# 13_eMMC_Flash.net
KiCad netlist of a schematic drawn in Altium Designer
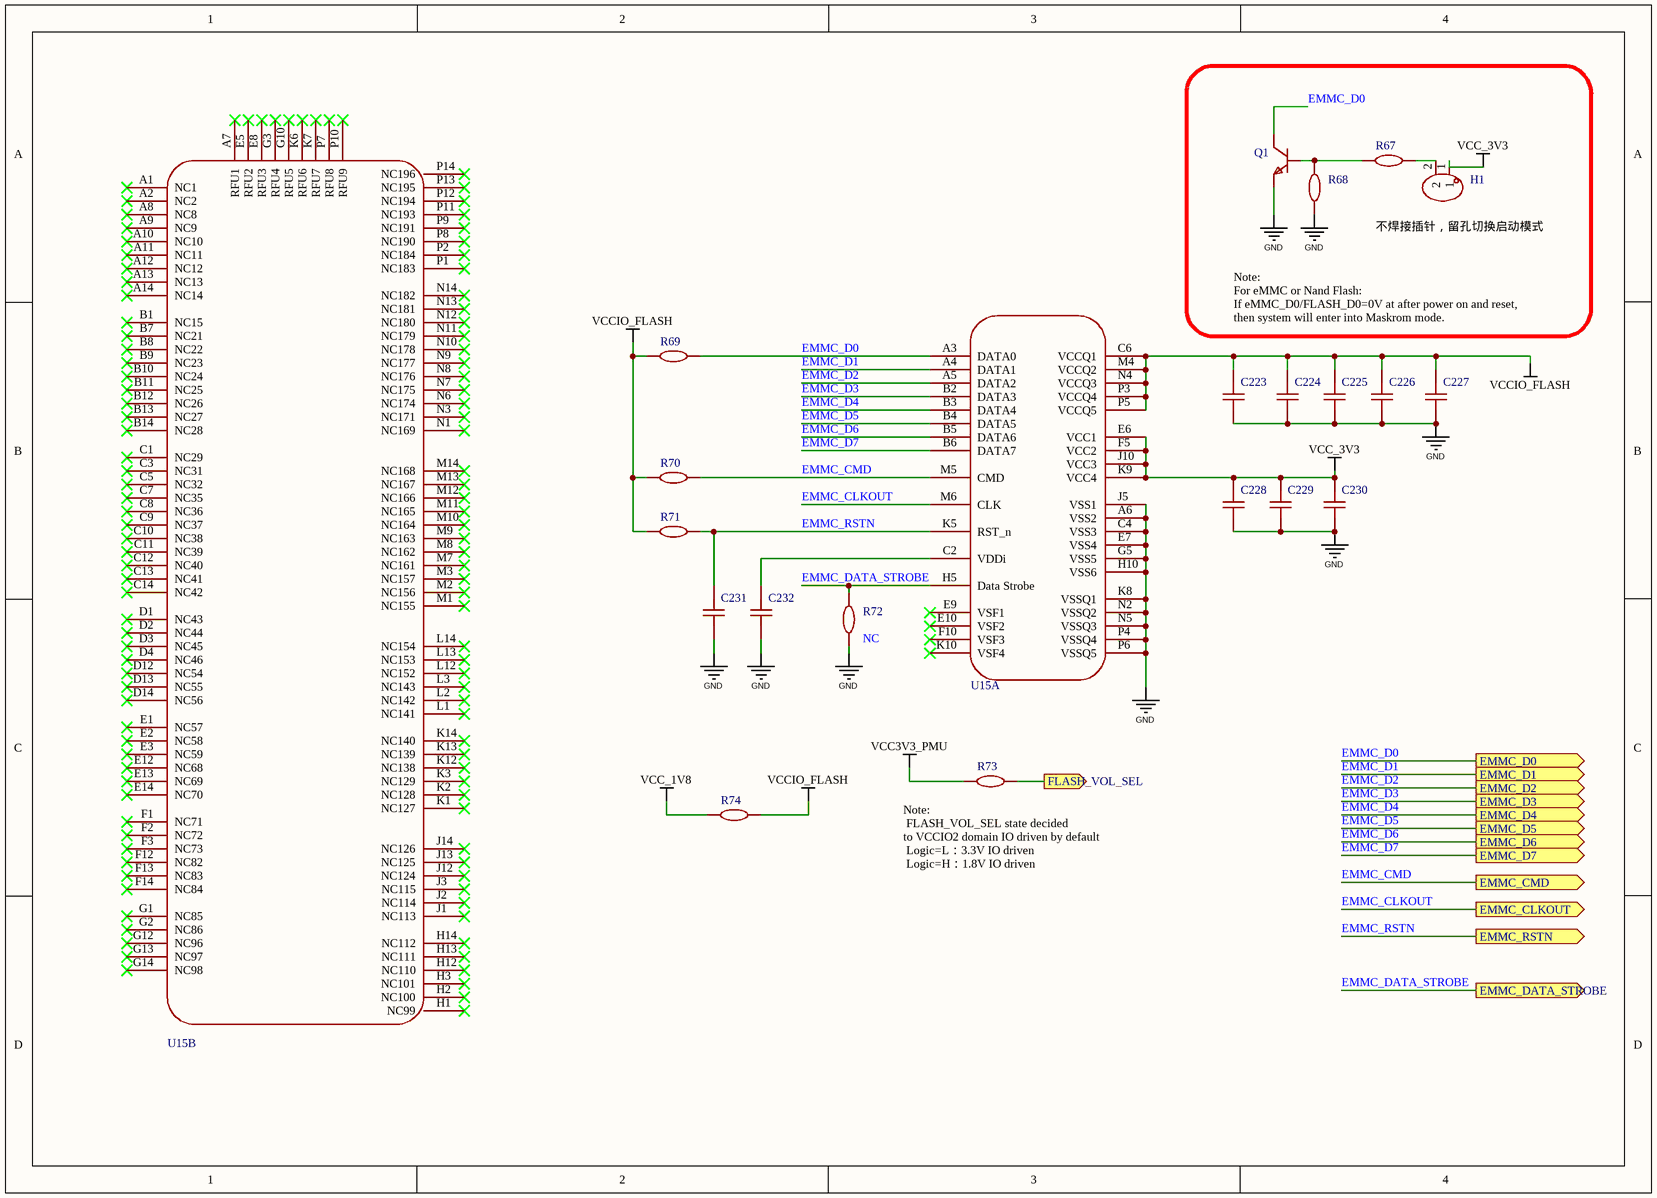
[diagram p0: 13_eMMC Flash.schdoc]

(export (version "E")
  (design (tool "Eeschema 10.0.6"))
  (components
    (comp (ref "C223")
      (value "100nF")
      (footprint "C0402")
      (description "容值:100nF;精度:±10%;额定电压:50V;材质(温度系数):X7R;")
      (fields
        (field (name "MANUFACTURER") "SAMSUNG(三星)")
        (field (name "MANUFACTURER PART") "CL05B104KB54PNC")
      )
      (libsource (lib "altium-import") (part "root_1_CL05B104KB54PNC_"))
    )
    (comp (ref "C224")
      (value "100nF")
      (footprint "C0402")
      (description "容值:100nF;精度:±10%;额定电压:50V;材质(温度系数):X7R;")
      (fields
        (field (name "MANUFACTURER") "SAMSUNG(三星)")
        (field (name "MANUFACTURER PART") "CL05B104KB54PNC")
      )
      (libsource (lib "altium-import") (part "root_1_CL05B104KB54PNC_"))
    )
    (comp (ref "C225")
      (value "100nF")
      (footprint "C0402")
      (description "容值:100nF;精度:±10%;额定电压:50V;材质(温度系数):X7R;")
      (fields
        (field (name "MANUFACTURER") "SAMSUNG(三星)")
        (field (name "MANUFACTURER PART") "CL05B104KB54PNC")
      )
      (libsource (lib "altium-import") (part "root_1_CL05B104KB54PNC_"))
    )
    (comp (ref "C226")
      (value "100nF")
      (footprint "C0402")
      (description "容值:100nF;精度:±10%;额定电压:50V;材质(温度系数):X7R;")
      (fields
        (field (name "MANUFACTURER") "SAMSUNG(三星)")
        (field (name "MANUFACTURER PART") "CL05B104KB54PNC")
      )
      (libsource (lib "altium-import") (part "root_1_CL05B104KB54PNC_"))
    )
    (comp (ref "C227")
      (value "4.7uF")
      (footprint "C0402")
      (description "容值:4.7uF;精度:±10%;额定电压:10V;材质(温度系数):X5R;")
      (fields
        (field (name "MANUFACTURER") "SAMSUNG(三星)")
        (field (name "MANUFACTURER PART") "CL05A475KP5NRNC")
      )
      (libsource (lib "altium-import") (part "root_0_CL05A475KP5NRNC_"))
    )
    (comp (ref "C228")
      (value "100nF")
      (footprint "C0402")
      (description "容值:100nF;精度:±10%;额定电压:50V;材质(温度系数):X7R;")
      (fields
        (field (name "MANUFACTURER") "SAMSUNG(三星)")
        (field (name "MANUFACTURER PART") "CL05B104KB54PNC")
      )
      (libsource (lib "altium-import") (part "root_1_CL05B104KB54PNC_"))
    )
    (comp (ref "C229")
      (value "100nF")
      (footprint "C0402")
      (description "容值:100nF;精度:±10%;额定电压:50V;材质(温度系数):X7R;")
      (fields
        (field (name "MANUFACTURER") "SAMSUNG(三星)")
        (field (name "MANUFACTURER PART") "CL05B104KB54PNC")
      )
      (libsource (lib "altium-import") (part "root_1_CL05B104KB54PNC_"))
    )
    (comp (ref "C230")
      (value "4.7uF")
      (footprint "C0402")
      (description "容值:4.7uF;精度:±10%;额定电压:10V;材质(温度系数):X5R;")
      (fields
        (field (name "MANUFACTURER") "SAMSUNG(三星)")
        (field (name "MANUFACTURER PART") "CL05A475KP5NRNC")
      )
      (libsource (lib "altium-import") (part "root_0_CL05A475KP5NRNC_"))
    )
    (comp (ref "C231")
      (value "100nF")
      (footprint "C0402")
      (description "容值:100nF;精度:±10%;额定电压:50V;材质(温度系数):X7R;")
      (fields
        (field (name "MANUFACTURER") "SAMSUNG(三星)")
        (field (name "MANUFACTURER PART") "CL05B104KB54PNC")
      )
      (libsource (lib "altium-import") (part "root_1_CL05B104KB54PNC_"))
    )
    (comp (ref "C232")
      (value "2.2uF")
      (footprint "C0402")
      (description "容值:2.2uF;精度:±10%;额定电压:16V;材质(温度系数):X5R;")
      (fields
        (field (name "MANUFACTURER") "SAMSUNG(三星)")
        (field (name "MANUFACTURER PART") "CL05A225KO5NQNC")
      )
      (libsource (lib "altium-import") (part "root_1_CL05A225KO5NQNC_"))
    )
    (comp (ref "H1")
      (value "PZ254V-11-02P")
      (footprint "HDR-TH_2P-P2.54-V-M")
      (fields (field (name "MANUFACTURER") "XFCN(兴飞)"))
      (libsource (lib "altium-import") (part "root_3_PZ254V-11-02P_"))
    )
    (comp (ref "Q1")
      (value "SS8050")
      (footprint "SOT-23-3_L2.9-W1.3-P1.90-LS2.4-BR")
      (description "晶体管类型:NPN;集电极电流(Ic):1.5A;集射极击穿电压(Vceo):25V;功率(Pd):300mW;直流电流增益(hFE@Ic,Vce):200@100mA,1V;")
      (fields (field (name "MANUFACTURER") "CJ(江苏长电/长晶)"))
      (libsource (lib "altium-import") (part "root_0_mirrored_SS8050_C2150_"))
    )
    (comp (ref "R67")
      (value "10kΩ")
      (footprint "R0402")
      (description "电阻类型:厚膜电阻;阻值:10kΩ;精度:±1%;功率:62.5mW;最大工作电压:50V;温度系数:±100ppm/℃;")
      (fields
        (field (name "MANUFACTURER") "UNI-ROYAL(厚声)")
        (field (name "MANUFACTURER PART") "0402WGF1002TCE")
      )
      (libsource (lib "altium-import") (part "root_0_0402WGF1002TCE_"))
    )
    (comp (ref "R68")
      (value "47kΩ")
      (footprint "R0402")
      (description "电阻类型:厚膜电阻;阻值:47kΩ;精度:±1%;功率:62.5mW;最大工作电压:50V;温度系数:±100ppm/℃;")
      (fields
        (field (name "MANUFACTURER") "UNI-ROYAL(厚声)")
        (field (name "MANUFACTURER PART") "0402WGF4702TCE")
      )
      (libsource (lib "altium-import") (part "root_1_0402WGF4702TCE_"))
    )
    (comp (ref "R69")
      (value "10kΩ")
      (footprint "R0402")
      (description "电阻类型:厚膜电阻;阻值:10kΩ;精度:±1%;功率:62.5mW;最大工作电压:50V;温度系数:±100ppm/℃;")
      (fields
        (field (name "MANUFACTURER") "UNI-ROYAL(厚声)")
        (field (name "MANUFACTURER PART") "0402WGF1002TCE")
      )
      (libsource (lib "altium-import") (part "root_0_0402WGF1002TCE_"))
    )
    (comp (ref "R70")
      (value "10kΩ")
      (footprint "R0402")
      (description "电阻类型:厚膜电阻;阻值:10kΩ;精度:±1%;功率:62.5mW;最大工作电压:50V;温度系数:±100ppm/℃;")
      (fields
        (field (name "MANUFACTURER") "UNI-ROYAL(厚声)")
        (field (name "MANUFACTURER PART") "0402WGF1002TCE")
      )
      (libsource (lib "altium-import") (part "root_0_0402WGF1002TCE_"))
    )
    (comp (ref "R71")
      (value "10kΩ")
      (footprint "R0402")
      (description "电阻类型:厚膜电阻;阻值:10kΩ;精度:±1%;功率:62.5mW;最大工作电压:50V;温度系数:±100ppm/℃;")
      (fields
        (field (name "MANUFACTURER") "UNI-ROYAL(厚声)")
        (field (name "MANUFACTURER PART") "0402WGF1002TCE")
      )
      (libsource (lib "altium-import") (part "root_0_0402WGF1002TCE_"))
    )
    (comp (ref "R72")
      (value "47kΩ")
      (footprint "R0402")
      (description "电阻类型:厚膜电阻;阻值:47kΩ;精度:±1%;功率:62.5mW;最大工作电压:50V;温度系数:±100ppm/℃;")
      (fields
        (field (name "MANUFACTURER") "UNI-ROYAL(厚声)")
        (field (name "MANUFACTURER PART") "0402WGF4702TCE")
      )
      (libsource (lib "altium-import") (part "root_1_0402WGF4702TCE_"))
    )
    (comp (ref "R73")
      (value "10kΩ")
      (footprint "R0402")
      (description "电阻类型:厚膜电阻;阻值:10kΩ;精度:±1%;功率:62.5mW;最大工作电压:50V;温度系数:±100ppm/℃;")
      (fields
        (field (name "MANUFACTURER") "UNI-ROYAL(厚声)")
        (field (name "MANUFACTURER PART") "0402WGF1002TCE")
      )
      (libsource (lib "altium-import") (part "root_0_0402WGF1002TCE_"))
    )
    (comp (ref "R74")
      (value "0Ω")
      (footprint "R0603")
      (description "电阻类型:厚膜电阻;阻值:0Ω;精度:±1%;功率:100mW;最大工作电压:75V;")
      (fields
        (field (name "MANUFACTURER") "UNI-ROYAL(厚声)")
        (field (name "MANUFACTURER PART") "0603WAF0000T5E")
      )
      (libsource (lib "altium-import") (part "root_0_0603WAF0000T5E_"))
    )
    (comp (ref "U15")
      (value "KLMBG2JETD-B041")
      (footprint "FBGA-153_L8.5-W8.0-P0.50_EMMC32G-KC30-01")
      (libsource (lib "RK3568核心板") (part "KLMBG2JETD-B041"))
    )
  )
  (nets
    (net (code "1") (name "/EMMC_CLKOUT") (class "Default")
      (node (ref "U15") (pin "M6") (pinfunction "CLK_M6") (pintype "passive"))
    )
    (net (code "2") (name "/EMMC_CMD") (class "Default")
      (node (ref "R70") (pin "2") (pinfunction "2_2") (pintype "passive"))
      (node (ref "U15") (pin "M5") (pinfunction "CMD_M5") (pintype "passive"))
    )
    (net (code "3") (name "/EMMC_D0") (class "Default")
      (node (ref "Q1") (pin "3") (pinfunction "C_3") (pintype "passive"))
      (node (ref "R69") (pin "2") (pinfunction "2_2") (pintype "passive"))
      (node (ref "U15") (pin "A3") (pinfunction "DATA0_A3") (pintype "passive"))
    )
    (net (code "4") (name "/EMMC_D1") (class "Default")
      (node (ref "U15") (pin "A4") (pinfunction "DATA1_A4") (pintype "passive"))
    )
    (net (code "5") (name "/EMMC_D2") (class "Default")
      (node (ref "U15") (pin "A5") (pinfunction "DATA2_A5") (pintype "passive"))
    )
    (net (code "6") (name "/EMMC_D3") (class "Default")
      (node (ref "U15") (pin "B2") (pinfunction "DATA3_B2") (pintype "passive"))
    )
    (net (code "7") (name "/EMMC_D4") (class "Default")
      (node (ref "U15") (pin "B3") (pinfunction "DATA4_B3") (pintype "passive"))
    )
    (net (code "8") (name "/EMMC_D5") (class "Default")
      (node (ref "U15") (pin "B4") (pinfunction "DATA5_B4") (pintype "passive"))
    )
    (net (code "9") (name "/EMMC_D6") (class "Default")
      (node (ref "U15") (pin "B5") (pinfunction "DATA6_B5") (pintype "passive"))
    )
    (net (code "10") (name "/EMMC_D7") (class "Default")
      (node (ref "U15") (pin "B6") (pinfunction "DATA7_B6") (pintype "passive"))
    )
    (net (code "11") (name "/EMMC_DATA_STROBE") (class "Default")
      (node (ref "R72") (pin "2") (pinfunction "2_2") (pintype "passive"))
      (node (ref "U15") (pin "H5") (pinfunction "Data_Strobe_H5") (pintype "passive"))
    )
    (net (code "12") (name "/EMMC_RSTN") (class "Default")
      (node (ref "C231") (pin "2") (pinfunction "2_2") (pintype "passive"))
      (node (ref "R71") (pin "2") (pinfunction "2_2") (pintype "passive"))
      (node (ref "U15") (pin "K5") (pinfunction "RST_n_K5") (pintype "passive"))
    )
    (net (code "13") (name "/FLASH_VOL_SEL") (class "Default")
      (node (ref "R73") (pin "2") (pinfunction "2_2") (pintype "passive"))
    )
    (net (code "14") (name "GND") (class "Default")
      (node (ref "C223") (pin "1") (pinfunction "1_1") (pintype "passive"))
      (node (ref "C224") (pin "1") (pinfunction "1_1") (pintype "passive"))
      (node (ref "C225") (pin "1") (pinfunction "1_1") (pintype "passive"))
      (node (ref "C226") (pin "1") (pinfunction "1_1") (pintype "passive"))
      (node (ref "C227") (pin "1") (pinfunction "1_1") (pintype "passive"))
      (node (ref "C228") (pin "1") (pinfunction "1_1") (pintype "passive"))
      (node (ref "C229") (pin "1") (pinfunction "1_1") (pintype "passive"))
      (node (ref "C230") (pin "1") (pinfunction "1_1") (pintype "passive"))
      (node (ref "C231") (pin "1") (pinfunction "1_1") (pintype "passive"))
      (node (ref "C232") (pin "2") (pinfunction "2_2") (pintype "passive"))
      (node (ref "Q1") (pin "2") (pinfunction "E_2") (pintype "passive"))
      (node (ref "R68") (pin "1") (pinfunction "1_1") (pintype "passive"))
      (node (ref "R72") (pin "1") (pinfunction "1_1") (pintype "passive"))
      (node (ref "U15") (pin "A6") (pinfunction "VSS2_A6") (pintype "passive"))
      (node (ref "U15") (pin "C4") (pinfunction "VSS3_C4") (pintype "passive"))
      (node (ref "U15") (pin "E7") (pinfunction "VSS4_E7") (pintype "passive"))
      (node (ref "U15") (pin "G5") (pinfunction "VSS5_G5") (pintype "passive"))
      (node (ref "U15") (pin "H10") (pinfunction "VSS6_H10") (pintype "passive"))
      (node (ref "U15") (pin "J5") (pinfunction "VSS1_J5") (pintype "passive"))
      (node (ref "U15") (pin "K8") (pinfunction "VSSQ1_K8") (pintype "passive"))
      (node (ref "U15") (pin "N2") (pinfunction "VSSQ2_N2") (pintype "passive"))
      (node (ref "U15") (pin "N5") (pinfunction "VSSQ3_N5") (pintype "passive"))
      (node (ref "U15") (pin "P4") (pinfunction "VSSQ4_P4") (pintype "passive"))
      (node (ref "U15") (pin "P6") (pinfunction "VSSQ5_P6") (pintype "passive"))
    )
    (net (code "15") (name "Net-(H1-Pad2)") (class "Default")
      (node (ref "H1") (pin "2") (pinfunction "2_2") (pintype "passive"))
      (node (ref "R67") (pin "2") (pinfunction "2_2") (pintype "passive"))
    )
    (net (code "16") (name "Net-(Q1-B)") (class "Default")
      (node (ref "Q1") (pin "1") (pinfunction "B_1") (pintype "passive"))
      (node (ref "R67") (pin "1") (pinfunction "1_1") (pintype "passive"))
      (node (ref "R68") (pin "2") (pinfunction "2_2") (pintype "passive"))
    )
    (net (code "17") (name "Net-(U15A-VDDi)") (class "Default")
      (node (ref "C232") (pin "1") (pinfunction "1_1") (pintype "passive"))
      (node (ref "U15") (pin "C2") (pinfunction "VDDi_C2") (pintype "passive"))
    )
    (net (code "18") (name "VCC3V3_PMU") (class "Default")
      (node (ref "R73") (pin "1") (pinfunction "1_1") (pintype "passive"))
    )
    (net (code "19") (name "VCCIO_FLASH") (class "Default")
      (node (ref "C223") (pin "2") (pinfunction "2_2") (pintype "passive"))
      (node (ref "C224") (pin "2") (pinfunction "2_2") (pintype "passive"))
      (node (ref "C225") (pin "2") (pinfunction "2_2") (pintype "passive"))
      (node (ref "C226") (pin "2") (pinfunction "2_2") (pintype "passive"))
      (node (ref "C227") (pin "2") (pinfunction "2_2") (pintype "passive"))
      (node (ref "R69") (pin "1") (pinfunction "1_1") (pintype "passive"))
      (node (ref "R70") (pin "1") (pinfunction "1_1") (pintype "passive"))
      (node (ref "R71") (pin "1") (pinfunction "1_1") (pintype "passive"))
      (node (ref "R74") (pin "2") (pinfunction "2_2") (pintype "passive"))
      (node (ref "U15") (pin "C6") (pinfunction "VCCQ1_C6") (pintype "passive"))
      (node (ref "U15") (pin "M4") (pinfunction "VCCQ2_M4") (pintype "passive"))
      (node (ref "U15") (pin "N4") (pinfunction "VCCQ3_N4") (pintype "passive"))
      (node (ref "U15") (pin "P3") (pinfunction "VCCQ4_P3") (pintype "passive"))
      (node (ref "U15") (pin "P5") (pinfunction "VCCQ5_P5") (pintype "passive"))
    )
    (net (code "20") (name "VCC_1V8") (class "Default")
      (node (ref "R74") (pin "1") (pinfunction "1_1") (pintype "passive"))
    )
    (net (code "21") (name "VCC_3V3") (class "Default")
      (node (ref "C228") (pin "2") (pinfunction "2_2") (pintype "passive"))
      (node (ref "C229") (pin "2") (pinfunction "2_2") (pintype "passive"))
      (node (ref "C230") (pin "2") (pinfunction "2_2") (pintype "passive"))
      (node (ref "H1") (pin "1") (pinfunction "1_1") (pintype "passive"))
      (node (ref "U15") (pin "E6") (pinfunction "VCC1_E6") (pintype "passive"))
      (node (ref "U15") (pin "F5") (pinfunction "VCC2_F5") (pintype "passive"))
      (node (ref "U15") (pin "J10") (pinfunction "VCC3_J10") (pintype "passive"))
      (node (ref "U15") (pin "K9") (pinfunction "VCC4_K9") (pintype "passive"))
    )
    (net (code "22") (name "unconnected-(U15A-VSF1-PadE9)") (class "Default")
      (node (ref "U15") (pin "E9") (pinfunction "VSF1_E9") (pintype "passive+no_connect"))
    )
    (net (code "23") (name "unconnected-(U15A-VSF2-PadE10)") (class "Default")
      (node (ref "U15") (pin "E10") (pinfunction "VSF2_E10") (pintype "passive+no_connect"))
    )
    (net (code "24") (name "unconnected-(U15A-VSF3-PadF10)") (class "Default")
      (node (ref "U15") (pin "F10") (pinfunction "VSF3_F10") (pintype "passive+no_connect"))
    )
    (net (code "25") (name "unconnected-(U15A-VSF4-PadK10)") (class "Default")
      (node (ref "U15") (pin "K10") (pinfunction "VSF4_K10") (pintype "passive+no_connect"))
    )
    (net (code "26") (name "unconnected-(U15B-NC1-PadA1)") (class "Default")
      (node (ref "U15") (pin "A1") (pinfunction "NC1_A1") (pintype "passive+no_connect"))
    )
    (net (code "27") (name "unconnected-(U15B-NC2-PadA2)") (class "Default")
      (node (ref "U15") (pin "A2") (pinfunction "NC2_A2") (pintype "passive+no_connect"))
    )
    (net (code "28") (name "unconnected-(U15B-NC8-PadA8)") (class "Default")
      (node (ref "U15") (pin "A8") (pinfunction "NC8_A8") (pintype "passive+no_connect"))
    )
    (net (code "29") (name "unconnected-(U15B-NC9-PadA9)") (class "Default")
      (node (ref "U15") (pin "A9") (pinfunction "NC9_A9") (pintype "passive+no_connect"))
    )
    (net (code "30") (name "unconnected-(U15B-NC10-PadA10)") (class "Default")
      (node (ref "U15") (pin "A10") (pinfunction "NC10_A10") (pintype "passive+no_connect"))
    )
    (net (code "31") (name "unconnected-(U15B-NC11-PadA11)") (class "Default")
      (node (ref "U15") (pin "A11") (pinfunction "NC11_A11") (pintype "passive+no_connect"))
    )
    (net (code "32") (name "unconnected-(U15B-NC12-PadA12)") (class "Default")
      (node (ref "U15") (pin "A12") (pinfunction "NC12_A12") (pintype "passive+no_connect"))
    )
    (net (code "33") (name "unconnected-(U15B-NC13-PadA13)") (class "Default")
      (node (ref "U15") (pin "A13") (pinfunction "NC13_A13") (pintype "passive+no_connect"))
    )
    (net (code "34") (name "unconnected-(U15B-NC14-PadA14)") (class "Default")
      (node (ref "U15") (pin "A14") (pinfunction "NC14_A14") (pintype "passive+no_connect"))
    )
    (net (code "35") (name "unconnected-(U15B-NC15-PadB1)") (class "Default")
      (node (ref "U15") (pin "B1") (pinfunction "NC15_B1") (pintype "passive+no_connect"))
    )
    (net (code "36") (name "unconnected-(U15B-NC21-PadB7)") (class "Default")
      (node (ref "U15") (pin "B7") (pinfunction "NC21_B7") (pintype "passive+no_connect"))
    )
    (net (code "37") (name "unconnected-(U15B-NC22-PadB8)") (class "Default")
      (node (ref "U15") (pin "B8") (pinfunction "NC22_B8") (pintype "passive+no_connect"))
    )
    (net (code "38") (name "unconnected-(U15B-NC23-PadB9)") (class "Default")
      (node (ref "U15") (pin "B9") (pinfunction "NC23_B9") (pintype "passive+no_connect"))
    )
    (net (code "39") (name "unconnected-(U15B-NC24-PadB10)") (class "Default")
      (node (ref "U15") (pin "B10") (pinfunction "NC24_B10") (pintype "passive+no_connect"))
    )
    (net (code "40") (name "unconnected-(U15B-NC25-PadB11)") (class "Default")
      (node (ref "U15") (pin "B11") (pinfunction "NC25_B11") (pintype "passive+no_connect"))
    )
    (net (code "41") (name "unconnected-(U15B-NC26-PadB12)") (class "Default")
      (node (ref "U15") (pin "B12") (pinfunction "NC26_B12") (pintype "passive+no_connect"))
    )
    (net (code "42") (name "unconnected-(U15B-NC27-PadB13)") (class "Default")
      (node (ref "U15") (pin "B13") (pinfunction "NC27_B13") (pintype "passive+no_connect"))
    )
    (net (code "43") (name "unconnected-(U15B-NC28-PadB14)") (class "Default")
      (node (ref "U15") (pin "B14") (pinfunction "NC28_B14") (pintype "passive+no_connect"))
    )
    (net (code "44") (name "unconnected-(U15B-NC29-PadC1)") (class "Default")
      (node (ref "U15") (pin "C1") (pinfunction "NC29_C1") (pintype "passive+no_connect"))
    )
    (net (code "45") (name "unconnected-(U15B-NC31-PadC3)") (class "Default")
      (node (ref "U15") (pin "C3") (pinfunction "NC31_C3") (pintype "passive+no_connect"))
    )
    (net (code "46") (name "unconnected-(U15B-NC32-PadC5)") (class "Default")
      (node (ref "U15") (pin "C5") (pinfunction "NC32_C5") (pintype "passive+no_connect"))
    )
    (net (code "47") (name "unconnected-(U15B-NC35-PadC7)") (class "Default")
      (node (ref "U15") (pin "C7") (pinfunction "NC35_C7") (pintype "passive+no_connect"))
    )
    (net (code "48") (name "unconnected-(U15B-NC36-PadC8)") (class "Default")
      (node (ref "U15") (pin "C8") (pinfunction "NC36_C8") (pintype "passive+no_connect"))
    )
    (net (code "49") (name "unconnected-(U15B-NC37-PadC9)") (class "Default")
      (node (ref "U15") (pin "C9") (pinfunction "NC37_C9") (pintype "passive+no_connect"))
    )
    (net (code "50") (name "unconnected-(U15B-NC38-PadC10)") (class "Default")
      (node (ref "U15") (pin "C10") (pinfunction "NC38_C10") (pintype "passive+no_connect"))
    )
    (net (code "51") (name "unconnected-(U15B-NC39-PadC11)") (class "Default")
      (node (ref "U15") (pin "C11") (pinfunction "NC39_C11") (pintype "passive+no_connect"))
    )
    (net (code "52") (name "unconnected-(U15B-NC40-PadC12)") (class "Default")
      (node (ref "U15") (pin "C12") (pinfunction "NC40_C12") (pintype "passive+no_connect"))
    )
    (net (code "53") (name "unconnected-(U15B-NC41-PadC13)") (class "Default")
      (node (ref "U15") (pin "C13") (pinfunction "NC41_C13") (pintype "passive+no_connect"))
    )
    (net (code "54") (name "unconnected-(U15B-NC42-PadC14)") (class "Default")
      (node (ref "U15") (pin "C14") (pinfunction "NC42_C14") (pintype "passive+no_connect"))
    )
    (net (code "55") (name "unconnected-(U15B-NC43-PadD1)") (class "Default")
      (node (ref "U15") (pin "D1") (pinfunction "NC43_D1") (pintype "passive+no_connect"))
    )
    (net (code "56") (name "unconnected-(U15B-NC44-PadD2)") (class "Default")
      (node (ref "U15") (pin "D2") (pinfunction "NC44_D2") (pintype "passive+no_connect"))
    )
    (net (code "57") (name "unconnected-(U15B-NC45-PadD3)") (class "Default")
      (node (ref "U15") (pin "D3") (pinfunction "NC45_D3") (pintype "passive+no_connect"))
    )
    (net (code "58") (name "unconnected-(U15B-NC46-PadD4)") (class "Default")
      (node (ref "U15") (pin "D4") (pinfunction "NC46_D4") (pintype "passive+no_connect"))
    )
    (net (code "59") (name "unconnected-(U15B-NC54-PadD12)") (class "Default")
      (node (ref "U15") (pin "D12") (pinfunction "NC54_D12") (pintype "passive+no_connect"))
    )
    (net (code "60") (name "unconnected-(U15B-NC55-PadD13)") (class "Default")
      (node (ref "U15") (pin "D13") (pinfunction "NC55_D13") (pintype "passive+no_connect"))
    )
    (net (code "61") (name "unconnected-(U15B-NC56-PadD14)") (class "Default")
      (node (ref "U15") (pin "D14") (pinfunction "NC56_D14") (pintype "passive+no_connect"))
    )
    (net (code "62") (name "unconnected-(U15B-NC57-PadE1)") (class "Default")
      (node (ref "U15") (pin "E1") (pinfunction "NC57_E1") (pintype "passive+no_connect"))
    )
    (net (code "63") (name "unconnected-(U15B-NC58-PadE2)") (class "Default")
      (node (ref "U15") (pin "E2") (pinfunction "NC58_E2") (pintype "passive+no_connect"))
    )
    (net (code "64") (name "unconnected-(U15B-NC59-PadE3)") (class "Default")
      (node (ref "U15") (pin "E3") (pinfunction "NC59_E3") (pintype "passive+no_connect"))
    )
    (net (code "65") (name "unconnected-(U15B-NC68-PadE12)") (class "Default")
      (node (ref "U15") (pin "E12") (pinfunction "NC68_E12") (pintype "passive+no_connect"))
    )
    (net (code "66") (name "unconnected-(U15B-NC69-PadE13)") (class "Default")
      (node (ref "U15") (pin "E13") (pinfunction "NC69_E13") (pintype "passive+no_connect"))
    )
    (net (code "67") (name "unconnected-(U15B-NC70-PadE14)") (class "Default")
      (node (ref "U15") (pin "E14") (pinfunction "NC70_E14") (pintype "passive+no_connect"))
    )
    (net (code "68") (name "unconnected-(U15B-NC71-PadF1)") (class "Default")
      (node (ref "U15") (pin "F1") (pinfunction "NC71_F1") (pintype "passive+no_connect"))
    )
    (net (code "69") (name "unconnected-(U15B-NC72-PadF2)") (class "Default")
      (node (ref "U15") (pin "F2") (pinfunction "NC72_F2") (pintype "passive+no_connect"))
    )
    (net (code "70") (name "unconnected-(U15B-NC73-PadF3)") (class "Default")
      (node (ref "U15") (pin "F3") (pinfunction "NC73_F3") (pintype "passive+no_connect"))
    )
    (net (code "71") (name "unconnected-(U15B-NC82-PadF12)") (class "Default")
      (node (ref "U15") (pin "F12") (pinfunction "NC82_F12") (pintype "passive+no_connect"))
    )
    (net (code "72") (name "unconnected-(U15B-NC83-PadF13)") (class "Default")
      (node (ref "U15") (pin "F13") (pinfunction "NC83_F13") (pintype "passive+no_connect"))
    )
    (net (code "73") (name "unconnected-(U15B-NC84-PadF14)") (class "Default")
      (node (ref "U15") (pin "F14") (pinfunction "NC84_F14") (pintype "passive+no_connect"))
    )
    (net (code "74") (name "unconnected-(U15B-NC85-PadG1)") (class "Default")
      (node (ref "U15") (pin "G1") (pinfunction "NC85_G1") (pintype "passive+no_connect"))
    )
    (net (code "75") (name "unconnected-(U15B-NC86-PadG2)") (class "Default")
      (node (ref "U15") (pin "G2") (pinfunction "NC86_G2") (pintype "passive+no_connect"))
    )
    (net (code "76") (name "unconnected-(U15B-NC96-PadG12)") (class "Default")
      (node (ref "U15") (pin "G12") (pinfunction "NC96_G12") (pintype "passive+no_connect"))
    )
    (net (code "77") (name "unconnected-(U15B-NC97-PadG13)") (class "Default")
      (node (ref "U15") (pin "G13") (pinfunction "NC97_G13") (pintype "passive+no_connect"))
    )
    (net (code "78") (name "unconnected-(U15B-NC98-PadG14)") (class "Default")
      (node (ref "U15") (pin "G14") (pinfunction "NC98_G14") (pintype "passive+no_connect"))
    )
    (net (code "79") (name "unconnected-(U15B-NC99-PadH1)") (class "Default")
      (node (ref "U15") (pin "H1") (pinfunction "NC99_H1") (pintype "passive+no_connect"))
    )
    (net (code "80") (name "unconnected-(U15B-NC100-PadH2)") (class "Default")
      (node (ref "U15") (pin "H2") (pinfunction "NC100_H2") (pintype "passive+no_connect"))
    )
    (net (code "81") (name "unconnected-(U15B-NC101-PadH3)") (class "Default")
      (node (ref "U15") (pin "H3") (pinfunction "NC101_H3") (pintype "passive+no_connect"))
    )
    (net (code "82") (name "unconnected-(U15B-NC110-PadH12)") (class "Default")
      (node (ref "U15") (pin "H12") (pinfunction "NC110_H12") (pintype "passive+no_connect"))
    )
    (net (code "83") (name "unconnected-(U15B-NC111-PadH13)") (class "Default")
      (node (ref "U15") (pin "H13") (pinfunction "NC111_H13") (pintype "passive+no_connect"))
    )
    (net (code "84") (name "unconnected-(U15B-NC112-PadH14)") (class "Default")
      (node (ref "U15") (pin "H14") (pinfunction "NC112_H14") (pintype "passive+no_connect"))
    )
    (net (code "85") (name "unconnected-(U15B-NC113-PadJ1)") (class "Default")
      (node (ref "U15") (pin "J1") (pinfunction "NC113_J1") (pintype "passive+no_connect"))
    )
    (net (code "86") (name "unconnected-(U15B-NC114-PadJ2)") (class "Default")
      (node (ref "U15") (pin "J2") (pinfunction "NC114_J2") (pintype "passive+no_connect"))
    )
    (net (code "87") (name "unconnected-(U15B-NC115-PadJ3)") (class "Default")
      (node (ref "U15") (pin "J3") (pinfunction "NC115_J3") (pintype "passive+no_connect"))
    )
    (net (code "88") (name "unconnected-(U15B-NC124-PadJ12)") (class "Default")
      (node (ref "U15") (pin "J12") (pinfunction "NC124_J12") (pintype "passive+no_connect"))
    )
    (net (code "89") (name "unconnected-(U15B-NC125-PadJ13)") (class "Default")
      (node (ref "U15") (pin "J13") (pinfunction "NC125_J13") (pintype "passive+no_connect"))
    )
    (net (code "90") (name "unconnected-(U15B-NC126-PadJ14)") (class "Default")
      (node (ref "U15") (pin "J14") (pinfunction "NC126_J14") (pintype "passive+no_connect"))
    )
    (net (code "91") (name "unconnected-(U15B-NC127-PadK1)") (class "Default")
      (node (ref "U15") (pin "K1") (pinfunction "NC127_K1") (pintype "passive+no_connect"))
    )
    (net (code "92") (name "unconnected-(U15B-NC128-PadK2)") (class "Default")
      (node (ref "U15") (pin "K2") (pinfunction "NC128_K2") (pintype "passive+no_connect"))
    )
    (net (code "93") (name "unconnected-(U15B-NC129-PadK3)") (class "Default")
      (node (ref "U15") (pin "K3") (pinfunction "NC129_K3") (pintype "passive+no_connect"))
    )
    (net (code "94") (name "unconnected-(U15B-NC138-PadK12)") (class "Default")
      (node (ref "U15") (pin "K12") (pinfunction "NC138_K12") (pintype "passive+no_connect"))
    )
    (net (code "95") (name "unconnected-(U15B-NC139-PadK13)") (class "Default")
      (node (ref "U15") (pin "K13") (pinfunction "NC139_K13") (pintype "passive+no_connect"))
    )
    (net (code "96") (name "unconnected-(U15B-NC140-PadK14)") (class "Default")
      (node (ref "U15") (pin "K14") (pinfunction "NC140_K14") (pintype "passive+no_connect"))
    )
    (net (code "97") (name "unconnected-(U15B-NC141-PadL1)") (class "Default")
      (node (ref "U15") (pin "L1") (pinfunction "NC141_L1") (pintype "passive+no_connect"))
    )
    (net (code "98") (name "unconnected-(U15B-NC142-PadL2)") (class "Default")
      (node (ref "U15") (pin "L2") (pinfunction "NC142_L2") (pintype "passive+no_connect"))
    )
    (net (code "99") (name "unconnected-(U15B-NC143-PadL3)") (class "Default")
      (node (ref "U15") (pin "L3") (pinfunction "NC143_L3") (pintype "passive+no_connect"))
    )
    (net (code "100") (name "unconnected-(U15B-NC152-PadL12)") (class "Default")
      (node (ref "U15") (pin "L12") (pinfunction "NC152_L12") (pintype "passive+no_connect"))
    )
    (net (code "101") (name "unconnected-(U15B-NC153-PadL13)") (class "Default")
      (node (ref "U15") (pin "L13") (pinfunction "NC153_L13") (pintype "passive+no_connect"))
    )
    (net (code "102") (name "unconnected-(U15B-NC154-PadL14)") (class "Default")
      (node (ref "U15") (pin "L14") (pinfunction "NC154_L14") (pintype "passive+no_connect"))
    )
    (net (code "103") (name "unconnected-(U15B-NC155-PadM1)") (class "Default")
      (node (ref "U15") (pin "M1") (pinfunction "NC155_M1") (pintype "passive+no_connect"))
    )
    (net (code "104") (name "unconnected-(U15B-NC156-PadM2)") (class "Default")
      (node (ref "U15") (pin "M2") (pinfunction "NC156_M2") (pintype "passive+no_connect"))
    )
    (net (code "105") (name "unconnected-(U15B-NC157-PadM3)") (class "Default")
      (node (ref "U15") (pin "M3") (pinfunction "NC157_M3") (pintype "passive+no_connect"))
    )
    (net (code "106") (name "unconnected-(U15B-NC161-PadM7)") (class "Default")
      (node (ref "U15") (pin "M7") (pinfunction "NC161_M7") (pintype "passive+no_connect"))
    )
    (net (code "107") (name "unconnected-(U15B-NC162-PadM8)") (class "Default")
      (node (ref "U15") (pin "M8") (pinfunction "NC162_M8") (pintype "passive+no_connect"))
    )
    (net (code "108") (name "unconnected-(U15B-NC163-PadM9)") (class "Default")
      (node (ref "U15") (pin "M9") (pinfunction "NC163_M9") (pintype "passive+no_connect"))
    )
    (net (code "109") (name "unconnected-(U15B-NC164-PadM10)") (class "Default")
      (node (ref "U15") (pin "M10") (pinfunction "NC164_M10") (pintype "passive+no_connect"))
    )
    (net (code "110") (name "unconnected-(U15B-NC165-PadM11)") (class "Default")
      (node (ref "U15") (pin "M11") (pinfunction "NC165_M11") (pintype "passive+no_connect"))
    )
    (net (code "111") (name "unconnected-(U15B-NC166-PadM12)") (class "Default")
      (node (ref "U15") (pin "M12") (pinfunction "NC166_M12") (pintype "passive+no_connect"))
    )
    (net (code "112") (name "unconnected-(U15B-NC167-PadM13)") (class "Default")
      (node (ref "U15") (pin "M13") (pinfunction "NC167_M13") (pintype "passive+no_connect"))
    )
    (net (code "113") (name "unconnected-(U15B-NC168-PadM14)") (class "Default")
      (node (ref "U15") (pin "M14") (pinfunction "NC168_M14") (pintype "passive+no_connect"))
    )
    (net (code "114") (name "unconnected-(U15B-NC169-PadN1)") (class "Default")
      (node (ref "U15") (pin "N1") (pinfunction "NC169_N1") (pintype "passive+no_connect"))
    )
    (net (code "115") (name "unconnected-(U15B-NC171-PadN3)") (class "Default")
      (node (ref "U15") (pin "N3") (pinfunction "NC171_N3") (pintype "passive+no_connect"))
    )
    (net (code "116") (name "unconnected-(U15B-NC174-PadN6)") (class "Default")
      (node (ref "U15") (pin "N6") (pinfunction "NC174_N6") (pintype "passive+no_connect"))
    )
    (net (code "117") (name "unconnected-(U15B-NC175-PadN7)") (class "Default")
      (node (ref "U15") (pin "N7") (pinfunction "NC175_N7") (pintype "passive+no_connect"))
    )
    (net (code "118") (name "unconnected-(U15B-NC176-PadN8)") (class "Default")
      (node (ref "U15") (pin "N8") (pinfunction "NC176_N8") (pintype "passive+no_connect"))
    )
    (net (code "119") (name "unconnected-(U15B-NC177-PadN9)") (class "Default")
      (node (ref "U15") (pin "N9") (pinfunction "NC177_N9") (pintype "passive+no_connect"))
    )
    (net (code "120") (name "unconnected-(U15B-NC178-PadN10)") (class "Default")
      (node (ref "U15") (pin "N10") (pinfunction "NC178_N10") (pintype "passive+no_connect"))
    )
    (net (code "121") (name "unconnected-(U15B-NC179-PadN11)") (class "Default")
      (node (ref "U15") (pin "N11") (pinfunction "NC179_N11") (pintype "passive+no_connect"))
    )
    (net (code "122") (name "unconnected-(U15B-NC180-PadN12)") (class "Default")
      (node (ref "U15") (pin "N12") (pinfunction "NC180_N12") (pintype "passive+no_connect"))
    )
    (net (code "123") (name "unconnected-(U15B-NC181-PadN13)") (class "Default")
      (node (ref "U15") (pin "N13") (pinfunction "NC181_N13") (pintype "passive+no_connect"))
    )
    (net (code "124") (name "unconnected-(U15B-NC182-PadN14)") (class "Default")
      (node (ref "U15") (pin "N14") (pinfunction "NC182_N14") (pintype "passive+no_connect"))
    )
    (net (code "125") (name "unconnected-(U15B-NC183-PadP1)") (class "Default")
      (node (ref "U15") (pin "P1") (pinfunction "NC183_P1") (pintype "passive+no_connect"))
    )
    (net (code "126") (name "unconnected-(U15B-NC184-PadP2)") (class "Default")
      (node (ref "U15") (pin "P2") (pinfunction "NC184_P2") (pintype "passive+no_connect"))
    )
    (net (code "127") (name "unconnected-(U15B-NC190-PadP8)") (class "Default")
      (node (ref "U15") (pin "P8") (pinfunction "NC190_P8") (pintype "passive+no_connect"))
    )
    (net (code "128") (name "unconnected-(U15B-NC191-PadP9)") (class "Default")
      (node (ref "U15") (pin "P9") (pinfunction "NC191_P9") (pintype "passive+no_connect"))
    )
    (net (code "129") (name "unconnected-(U15B-NC193-PadP11)") (class "Default")
      (node (ref "U15") (pin "P11") (pinfunction "NC193_P11") (pintype "passive+no_connect"))
    )
    (net (code "130") (name "unconnected-(U15B-NC194-PadP12)") (class "Default")
      (node (ref "U15") (pin "P12") (pinfunction "NC194_P12") (pintype "passive+no_connect"))
    )
    (net (code "131") (name "unconnected-(U15B-NC195-PadP13)") (class "Default")
      (node (ref "U15") (pin "P13") (pinfunction "NC195_P13") (pintype "passive+no_connect"))
    )
    (net (code "132") (name "unconnected-(U15B-NC196-PadP14)") (class "Default")
      (node (ref "U15") (pin "P14") (pinfunction "NC196_P14") (pintype "passive+no_connect"))
    )
    (net (code "133") (name "unconnected-(U15B-RFU1-PadA7)") (class "Default")
      (node (ref "U15") (pin "A7") (pinfunction "RFU1_A7") (pintype "passive+no_connect"))
    )
    (net (code "134") (name "unconnected-(U15B-RFU2-PadE5)") (class "Default")
      (node (ref "U15") (pin "E5") (pinfunction "RFU2_E5") (pintype "passive+no_connect"))
    )
    (net (code "135") (name "unconnected-(U15B-RFU3-PadE8)") (class "Default")
      (node (ref "U15") (pin "E8") (pinfunction "RFU3_E8") (pintype "passive+no_connect"))
    )
    (net (code "136") (name "unconnected-(U15B-RFU4-PadG3)") (class "Default")
      (node (ref "U15") (pin "G3") (pinfunction "RFU4_G3") (pintype "passive+no_connect"))
    )
    (net (code "137") (name "unconnected-(U15B-RFU5-PadG10)") (class "Default")
      (node (ref "U15") (pin "G10") (pinfunction "RFU5_G10") (pintype "passive+no_connect"))
    )
    (net (code "138") (name "unconnected-(U15B-RFU6-PadK6)") (class "Default")
      (node (ref "U15") (pin "K6") (pinfunction "RFU6_K6") (pintype "passive+no_connect"))
    )
    (net (code "139") (name "unconnected-(U15B-RFU7-PadK7)") (class "Default")
      (node (ref "U15") (pin "K7") (pinfunction "RFU7_K7") (pintype "passive+no_connect"))
    )
    (net (code "140") (name "unconnected-(U15B-RFU8-PadP7)") (class "Default")
      (node (ref "U15") (pin "P7") (pinfunction "RFU8_P7") (pintype "passive+no_connect"))
    )
    (net (code "141") (name "unconnected-(U15B-RFU9-PadP10)") (class "Default")
      (node (ref "U15") (pin "P10") (pinfunction "RFU9_P10") (pintype "passive+no_connect"))
    )
  )
)
